# 4-batteries.net
KiCad netlist of a schematic drawn in EAGLE
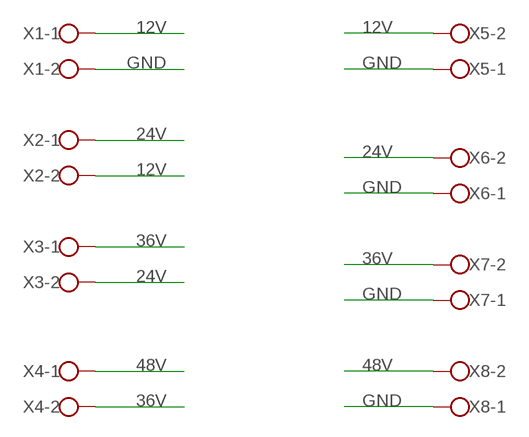
[diagram p0: schematic, sheet 1]

(export (version "E")
  (design (tool "Eeschema 10.0.6"))
  (components
    (comp (ref "X1")
      (value "ROSTA.POWER")
      (footprint "eagle-import:W239-302")
      (libsource (lib "eagle-import") (part "ROSTA.POWER"))
    )
    (comp (ref "X2")
      (value "ROSTA.POWER")
      (footprint "eagle-import:W239-302")
      (libsource (lib "eagle-import") (part "ROSTA.POWER"))
    )
    (comp (ref "X3")
      (value "ROSTA.POWER")
      (footprint "eagle-import:W239-302")
      (libsource (lib "eagle-import") (part "ROSTA.POWER"))
    )
    (comp (ref "X4")
      (value "ROSTA.POWER")
      (footprint "eagle-import:W239-302")
      (libsource (lib "eagle-import") (part "ROSTA.POWER"))
    )
    (comp (ref "X5")
      (value "ROSTA.POWER")
      (footprint "eagle-import:W239-302")
      (libsource (lib "eagle-import") (part "ROSTA.POWER"))
    )
    (comp (ref "X6")
      (value "ROSTA.POWER")
      (footprint "eagle-import:W239-302")
      (libsource (lib "eagle-import") (part "ROSTA.POWER"))
    )
    (comp (ref "X7")
      (value "ROSTA.POWER")
      (footprint "eagle-import:W239-302")
      (libsource (lib "eagle-import") (part "ROSTA.POWER"))
    )
    (comp (ref "X8")
      (value "ROSTA.POWER")
      (footprint "eagle-import:W239-302")
      (libsource (lib "eagle-import") (part "ROSTA.POWER"))
    )
  )
  (nets
    (net (code "1") (name "/12V") (class "Default")
      (node (ref "X1") (pin "1") (pinfunction "KL_1") (pintype "passive"))
      (node (ref "X2") (pin "2") (pinfunction "KL_2") (pintype "passive"))
      (node (ref "X5") (pin "2") (pinfunction "KL_2") (pintype "passive"))
    )
    (net (code "2") (name "/24V") (class "Default")
      (node (ref "X2") (pin "1") (pinfunction "KL_1") (pintype "passive"))
      (node (ref "X3") (pin "2") (pinfunction "KL_2") (pintype "passive"))
      (node (ref "X6") (pin "2") (pinfunction "KL_2") (pintype "passive"))
    )
    (net (code "3") (name "/36V") (class "Default")
      (node (ref "X3") (pin "1") (pinfunction "KL_1") (pintype "passive"))
      (node (ref "X4") (pin "2") (pinfunction "KL_2") (pintype "passive"))
      (node (ref "X7") (pin "2") (pinfunction "KL_2") (pintype "passive"))
    )
    (net (code "4") (name "/48V") (class "Default")
      (node (ref "X4") (pin "1") (pinfunction "KL_1") (pintype "passive"))
      (node (ref "X8") (pin "2") (pinfunction "KL_2") (pintype "passive"))
    )
    (net (code "5") (name "/GND") (class "Default")
      (node (ref "X1") (pin "2") (pinfunction "KL_2") (pintype "passive"))
      (node (ref "X5") (pin "1") (pinfunction "KL_1") (pintype "passive"))
      (node (ref "X6") (pin "1") (pinfunction "KL_1") (pintype "passive"))
      (node (ref "X7") (pin "1") (pinfunction "KL_1") (pintype "passive"))
      (node (ref "X8") (pin "1") (pinfunction "KL_1") (pintype "passive"))
    )
  )
)
